# Pressure_MCU407.net
KiCad netlist of a schematic drawn in Altium Designer
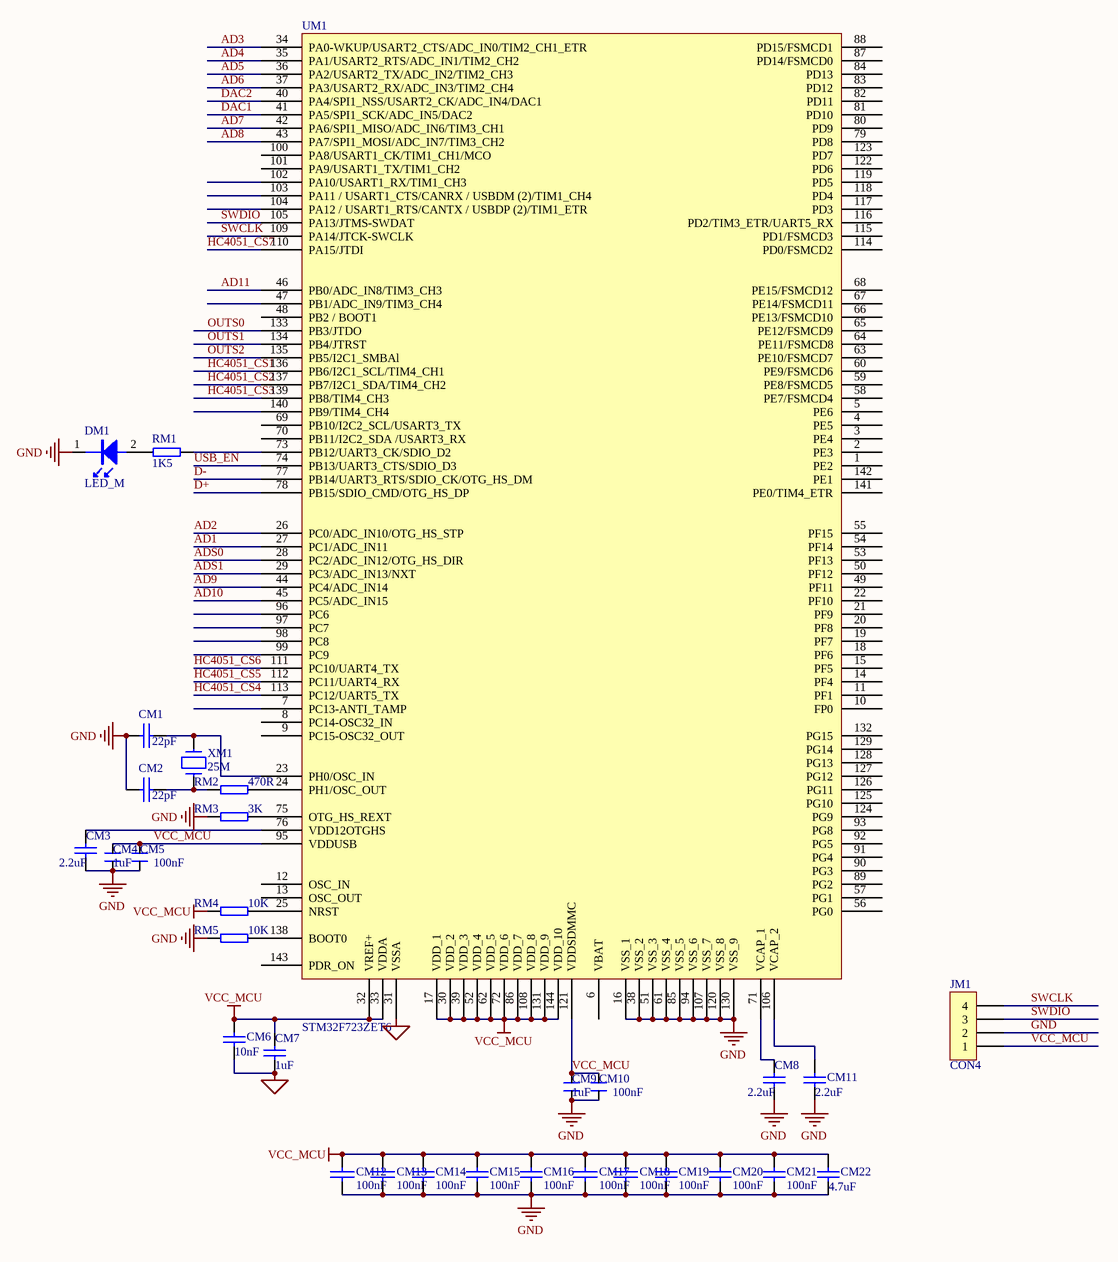
[diagram p0: Pressure_MCU407.SchDoc]

(export (version "E")
  (design (tool "Eeschema 10.0.6"))
  (components
    (comp (ref "CM1")
      (value "22pF")
      (footprint "C0603_HSC100")
      (description "Capacitor")
      (libsource (lib "*") (part "CAP"))
    )
    (comp (ref "CM2")
      (value "22pF")
      (footprint "c0603_HSC100")
      (description "Capacitor")
      (libsource (lib "*") (part "CAP"))
    )
    (comp (ref "CM3")
      (value "2.2uF")
      (footprint "C0805")
      (description "Capacitor")
      (fields (field (name "PUBLISHER") "Altium Limited"))
      (libsource (lib "*") (part "Cap"))
    )
    (comp (ref "CM4") (value "1uF") (footprint "C0603_HSC100") (libsource (lib "*") (part "CAP_M")))
    (comp (ref "CM5") (value "100nF") (footprint "C0603_HSC100") (libsource (lib "*") (part "CAP_M")))
    (comp (ref "CM6")
      (value "10nF")
      (footprint "c0603_HSC100")
      (description "Capacitor")
      (fields (field (name "PUBLISHER") "Altium Limited"))
      (libsource (lib "*") (part "Cap"))
    )
    (comp (ref "CM7")
      (value "1uF")
      (footprint "c0603_HSC100")
      (description "Capacitor")
      (fields (field (name "PUBLISHER") "Altium Limited"))
      (libsource (lib "*") (part "Cap"))
    )
    (comp (ref "CM8")
      (value "2.2uF")
      (footprint "C0805")
      (description "Capacitor")
      (fields (field (name "PUBLISHER") "Altium Limited"))
      (libsource (lib "*") (part "Cap"))
    )
    (comp (ref "CM9") (value "1uF") (footprint "C0603_HSC100") (libsource (lib "*") (part "CAP_M")))
    (comp (ref "CM10") (value "100nF") (footprint "C0603_HSC100") (libsource (lib "*") (part "CAP_M")))
    (comp (ref "CM11")
      (value "2.2uF")
      (footprint "C0805")
      (description "Capacitor")
      (fields (field (name "PUBLISHER") "Altium Limited"))
      (libsource (lib "*") (part "Cap"))
    )
    (comp (ref "CM12")
      (value "100nF")
      (footprint "c0603_HSC100")
      (description "Capacitor")
      (libsource (lib "*") (part "CAP"))
    )
    (comp (ref "CM13")
      (value "100nF")
      (footprint "c0603_HSC100")
      (description "Capacitor")
      (libsource (lib "*") (part "CAP"))
    )
    (comp (ref "CM14")
      (value "100nF")
      (footprint "c0603_HSC100")
      (description "Capacitor")
      (fields (field (name "PUBLISHER") "Altium Limited"))
      (libsource (lib "*") (part "Cap"))
    )
    (comp (ref "CM15")
      (value "100nF")
      (footprint "c0603_HSC100")
      (description "Capacitor")
      (fields (field (name "PUBLISHER") "Altium Limited"))
      (libsource (lib "*") (part "Cap"))
    )
    (comp (ref "CM16")
      (value "100nF")
      (footprint "c0603_HSC100")
      (description "Capacitor")
      (fields (field (name "PUBLISHER") "Altium Limited"))
      (libsource (lib "*") (part "Cap"))
    )
    (comp (ref "CM17")
      (value "100nF")
      (footprint "c0603_HSC100")
      (description "Capacitor")
      (libsource (lib "*") (part "CAP"))
    )
    (comp (ref "CM18")
      (value "100nF")
      (footprint "c0603_HSC100")
      (description "Capacitor")
      (libsource (lib "*") (part "CAP"))
    )
    (comp (ref "CM19")
      (value "100nF")
      (footprint "c0603_HSC100")
      (description "Capacitor")
      (fields (field (name "PUBLISHER") "Altium Limited"))
      (libsource (lib "*") (part "Cap"))
    )
    (comp (ref "CM20")
      (value "100nF")
      (footprint "c0603_HSC100")
      (description "Capacitor")
      (fields (field (name "PUBLISHER") "Altium Limited"))
      (libsource (lib "*") (part "Cap"))
    )
    (comp (ref "CM21")
      (value "100nF")
      (footprint "c0603_HSC100")
      (description "Capacitor")
      (fields (field (name "PUBLISHER") "Altium Limited"))
      (libsource (lib "*") (part "Cap"))
    )
    (comp (ref "CM22")
      (value "4.7uF")
      (footprint "C0805")
      (description "Capacitor")
      (fields (field (name "PUBLISHER") "Altium Limited"))
      (libsource (lib "*") (part "Cap"))
    )
    (comp (ref "DM1") (value "LED_M") (footprint "LED_HSC100") (libsource (lib "*") (part "LED_M")))
    (comp (ref "JM1")
      (value "CON4")
      (footprint "SIP_4M_1.27")
      (description "Connector")
      (libsource (lib "*") (part "CON4"))
    )
    (comp (ref "RM1") (value "1K5") (footprint "R0603_HSC100") (libsource (lib "*") (part "RES_M")))
    (comp (ref "RM2") (value "470R") (footprint "R0603_HSC100") (libsource (lib "*") (part "RES")))
    (comp (ref "RM3") (value "3K") (footprint "R0603_HSC100") (libsource (lib "*") (part "RES")))
    (comp (ref "RM4") (value "10K") (footprint "R0603_HSC100") (libsource (lib "*") (part "RES")))
    (comp (ref "RM5") (value "10K") (footprint "R0603_HSC100") (libsource (lib "*") (part "RES_M")))
    (comp (ref "UM1")
      (value "STM32F723ZET6")
      (footprint "LQFP144")
      (libsource (lib "MY_LIB") (part "STM32F723ZET6"))
    )
    (comp (ref "XM1")
      (value "25M")
      (footprint "CRYSTAL_SMD")
      (description "Crystal")
      (libsource (lib "*") (part "CRYSTAL"))
    )
  )
  (nets
    (net (code "1") (name "/AD1") (class "Default")
      (node (ref "UM1") (pin "27") (pinfunction "PC1/ADC_IN11_27") (pintype "passive"))
    )
    (net (code "2") (name "/AD2") (class "Default")
      (node (ref "UM1") (pin "26") (pinfunction "PC0/ADC_IN10/OTG_HS_STP_26") (pintype "passive"))
    )
    (net (code "3") (name "/AD3") (class "Default")
      (node (ref "UM1") (pin "34") (pinfunction "PA0-WKUP/USART2_CTS/ADC_IN0/TIM2_CH1_ETR_34") (pintype "passive"))
    )
    (net (code "4") (name "/AD4") (class "Default")
      (node (ref "UM1") (pin "35") (pinfunction "PA1/USART2_RTS/ADC_IN1/TIM2_CH2_35") (pintype "passive"))
    )
    (net (code "5") (name "/AD5") (class "Default")
      (node (ref "UM1") (pin "36") (pinfunction "PA2/USART2_TX/ADC_IN2/TIM2_CH3_36") (pintype "passive"))
    )
    (net (code "6") (name "/AD6") (class "Default")
      (node (ref "UM1") (pin "37") (pinfunction "PA3/USART2_RX/ADC_IN3/TIM2_CH4_37") (pintype "passive"))
    )
    (net (code "7") (name "/AD7") (class "Default")
      (node (ref "UM1") (pin "42") (pinfunction "PA6/SPI1_MISO/ADC_IN6/TIM3_CH1_42") (pintype "passive"))
    )
    (net (code "8") (name "/AD8") (class "Default")
      (node (ref "UM1") (pin "43") (pinfunction "PA7/SPI1_MOSI/ADC_IN7/TIM3_CH2_43") (pintype "passive"))
    )
    (net (code "9") (name "/AD9") (class "Default")
      (node (ref "UM1") (pin "44") (pinfunction "PC4/ADC_IN14_44") (pintype "passive"))
    )
    (net (code "10") (name "/AD10") (class "Default")
      (node (ref "UM1") (pin "45") (pinfunction "PC5/ADC_IN15_45") (pintype "passive"))
    )
    (net (code "11") (name "/AD11") (class "Default")
      (node (ref "UM1") (pin "46") (pinfunction "PB0/ADC_IN8/TIM3_CH3_46") (pintype "passive"))
    )
    (net (code "12") (name "/ADS0") (class "Default")
      (node (ref "UM1") (pin "28") (pinfunction "PC2/ADC_IN12/OTG_HS_DIR_28") (pintype "passive"))
    )
    (net (code "13") (name "/ADS1") (class "Default")
      (node (ref "UM1") (pin "29") (pinfunction "PC3/ADC_IN13/NXT_29") (pintype "passive"))
    )
    (net (code "14") (name "/D+") (class "Default")
      (node (ref "UM1") (pin "78") (pinfunction "PB15/SDIO_CMD/OTG_HS_DP_78") (pintype "passive"))
    )
    (net (code "15") (name "/D-") (class "Default")
      (node (ref "UM1") (pin "77") (pinfunction "PB14/UART3_RTS/SDIO_CK/OTG_HS_DM_77") (pintype "passive"))
    )
    (net (code "16") (name "/DAC1") (class "Default")
      (node (ref "UM1") (pin "41") (pinfunction "PA5/SPI1_SCK/ADC_IN5/DAC2_41") (pintype "passive"))
    )
    (net (code "17") (name "/DAC2") (class "Default")
      (node (ref "UM1") (pin "40") (pinfunction "PA4/SPI1_NSS/USART2_CK/ADC_IN4/DAC1_40") (pintype "passive"))
    )
    (net (code "18") (name "/HC4051_CS1") (class "Default")
      (node (ref "UM1") (pin "136") (pinfunction "PB6/I2C1_SCL/TIM4_CH1_136") (pintype "passive"))
    )
    (net (code "19") (name "/HC4051_CS2") (class "Default")
      (node (ref "UM1") (pin "137") (pinfunction "PB7/I2C1_SDA/TIM4_CH2_137") (pintype "passive"))
    )
    (net (code "20") (name "/HC4051_CS3") (class "Default")
      (node (ref "UM1") (pin "139") (pinfunction "PB8/TIM4_CH3_139") (pintype "passive"))
    )
    (net (code "21") (name "/HC4051_CS4") (class "Default")
      (node (ref "UM1") (pin "113") (pinfunction "PC12/UART5_TX_113") (pintype "passive"))
    )
    (net (code "22") (name "/HC4051_CS5") (class "Default")
      (node (ref "UM1") (pin "112") (pinfunction "PC11/UART4_RX_112") (pintype "passive"))
    )
    (net (code "23") (name "/HC4051_CS6") (class "Default")
      (node (ref "UM1") (pin "111") (pinfunction "PC10/UART4_TX_111") (pintype "passive"))
    )
    (net (code "24") (name "/HC4051_CS7") (class "Default")
      (node (ref "UM1") (pin "110") (pinfunction "PA15/JTDI_110") (pintype "passive"))
    )
    (net (code "25") (name "/OUTS0") (class "Default")
      (node (ref "UM1") (pin "133") (pinfunction "PB3/JTDO_133") (pintype "passive"))
    )
    (net (code "26") (name "/OUTS1") (class "Default")
      (node (ref "UM1") (pin "134") (pinfunction "PB4/JTRST_134") (pintype "passive"))
    )
    (net (code "27") (name "/OUTS2") (class "Default")
      (node (ref "UM1") (pin "135") (pinfunction "PB5/I2C1_SMBAl_135") (pintype "passive"))
    )
    (net (code "28") (name "/SWCLK") (class "Default")
      (node (ref "JM1") (pin "4") (pinfunction "4_4") (pintype "passive"))
      (node (ref "UM1") (pin "109") (pinfunction "PA14/JTCK-SWCLK_109") (pintype "passive"))
    )
    (net (code "29") (name "/SWDIO") (class "Default")
      (node (ref "JM1") (pin "3") (pinfunction "3_3") (pintype "passive"))
      (node (ref "UM1") (pin "105") (pinfunction "PA13/JTMS-SWDAT_105") (pintype "passive"))
    )
    (net (code "30") (name "/USB_EN") (class "Default")
      (node (ref "UM1") (pin "74") (pinfunction "PB13/UART3_CTS/SDIO_D3_74") (pintype "passive"))
    )
    (net (code "31") (name "AGND") (class "Default")
      (node (ref "CM6") (pin "2") (pinfunction "2_2") (pintype "passive"))
      (node (ref "CM7") (pin "2") (pinfunction "2_2") (pintype "passive"))
      (node (ref "UM1") (pin "31") (pinfunction "VSSA_31") (pintype "passive"))
    )
    (net (code "32") (name "GND") (class "Default")
      (node (ref "CM1") (pin "1") (pinfunction "1_1") (pintype "passive"))
      (node (ref "CM10") (pin "2") (pintype "passive"))
      (node (ref "CM11") (pin "1") (pinfunction "1_1") (pintype "passive"))
      (node (ref "CM12") (pin "2") (pinfunction "2_2") (pintype "passive"))
      (node (ref "CM13") (pin "2") (pinfunction "2_2") (pintype "passive"))
      (node (ref "CM14") (pin "1") (pinfunction "1_1") (pintype "passive"))
      (node (ref "CM15") (pin "1") (pinfunction "1_1") (pintype "passive"))
      (node (ref "CM16") (pin "1") (pinfunction "1_1") (pintype "passive"))
      (node (ref "CM17") (pin "2") (pinfunction "2_2") (pintype "passive"))
      (node (ref "CM18") (pin "2") (pinfunction "2_2") (pintype "passive"))
      (node (ref "CM19") (pin "1") (pinfunction "1_1") (pintype "passive"))
      (node (ref "CM2") (pin "1") (pinfunction "1_1") (pintype "passive"))
      (node (ref "CM20") (pin "1") (pinfunction "1_1") (pintype "passive"))
      (node (ref "CM21") (pin "1") (pinfunction "1_1") (pintype "passive"))
      (node (ref "CM22") (pin "1") (pinfunction "1_1") (pintype "passive"))
      (node (ref "CM3") (pin "1") (pinfunction "1_1") (pintype "passive"))
      (node (ref "CM4") (pin "2") (pintype "passive"))
      (node (ref "CM5") (pin "2") (pintype "passive"))
      (node (ref "CM8") (pin "1") (pinfunction "1_1") (pintype "passive"))
      (node (ref "CM9") (pin "2") (pintype "passive"))
      (node (ref "DM1") (pin "1") (pinfunction "1_1") (pintype "passive"))
      (node (ref "JM1") (pin "2") (pinfunction "2_2") (pintype "passive"))
      (node (ref "RM3") (pin "2") (pintype "passive"))
      (node (ref "RM5") (pin "1") (pintype "passive"))
      (node (ref "UM1") (pin "107") (pinfunction "VSS_7_107") (pintype "passive"))
      (node (ref "UM1") (pin "120") (pinfunction "VSS_8_120") (pintype "passive"))
      (node (ref "UM1") (pin "130") (pinfunction "VSS_9_130") (pintype "passive"))
      (node (ref "UM1") (pin "16") (pinfunction "VSS_1_16") (pintype "passive"))
      (node (ref "UM1") (pin "38") (pinfunction "VSS_2_38") (pintype "passive"))
      (node (ref "UM1") (pin "51") (pinfunction "VSS_3_51") (pintype "passive"))
      (node (ref "UM1") (pin "61") (pinfunction "VSS_4_61") (pintype "passive"))
      (node (ref "UM1") (pin "85") (pinfunction "VSS_5_85") (pintype "passive"))
      (node (ref "UM1") (pin "94") (pinfunction "VSS_6_94") (pintype "passive"))
    )
    (net (code "33") (name "Net-(CM2-Pad2)") (class "Default")
      (node (ref "CM2") (pin "2") (pinfunction "2_2") (pintype "passive"))
      (node (ref "RM2") (pin "2") (pintype "passive"))
      (node (ref "XM1") (pin "1") (pinfunction "1_1") (pintype "passive"))
    )
    (net (code "34") (name "Net-(DM1-Pad2)") (class "Default")
      (node (ref "DM1") (pin "2") (pinfunction "2_2") (pintype "passive"))
      (node (ref "RM1") (pin "2") (pintype "passive"))
    )
    (net (code "35") (name "Net-(UM1-BOOT0)") (class "Default")
      (node (ref "RM5") (pin "2") (pintype "passive"))
      (node (ref "UM1") (pin "138") (pinfunction "BOOT0_138") (pintype "passive"))
    )
    (net (code "36") (name "Net-(UM1-NRST)") (class "Default")
      (node (ref "RM4") (pin "1") (pintype "passive"))
      (node (ref "UM1") (pin "25") (pinfunction "NRST_25") (pintype "passive"))
    )
    (net (code "37") (name "Net-(UM1-OTG_HS_REXT)") (class "Default")
      (node (ref "RM3") (pin "1") (pintype "passive"))
      (node (ref "UM1") (pin "75") (pinfunction "OTG_HS_REXT_75") (pintype "passive"))
    )
    (net (code "38") (name "Net-(UM1-PB12{slash}UART3_CK{slash}SDIO_D2)") (class "Default")
      (node (ref "RM1") (pin "1") (pintype "passive"))
      (node (ref "UM1") (pin "73") (pinfunction "PB12/UART3_CK/SDIO_D2_73") (pintype "passive"))
    )
    (net (code "39") (name "Net-(UM1-PH0{slash}OSC_IN)") (class "Default")
      (node (ref "CM1") (pin "2") (pinfunction "2_2") (pintype "passive"))
      (node (ref "UM1") (pin "23") (pinfunction "PH0/OSC_IN_23") (pintype "passive"))
      (node (ref "XM1") (pin "2") (pinfunction "2_2") (pintype "passive"))
    )
    (net (code "40") (name "Net-(UM1-PH1{slash}OSC_OUT)") (class "Default")
      (node (ref "RM2") (pin "1") (pintype "passive"))
      (node (ref "UM1") (pin "24") (pinfunction "PH1/OSC_OUT_24") (pintype "passive"))
    )
    (net (code "41") (name "Net-(UM1-VCAP_1)") (class "Default")
      (node (ref "CM8") (pin "2") (pinfunction "2_2") (pintype "passive"))
      (node (ref "UM1") (pin "71") (pinfunction "VCAP_1_71") (pintype "passive"))
    )
    (net (code "42") (name "Net-(UM1-VCAP_2)") (class "Default")
      (node (ref "CM11") (pin "2") (pinfunction "2_2") (pintype "passive"))
      (node (ref "UM1") (pin "106") (pinfunction "VCAP_2_106") (pintype "passive"))
    )
    (net (code "43") (name "Net-(UM1-VDD12OTGHS)") (class "Default")
      (node (ref "CM3") (pin "2") (pinfunction "2_2") (pintype "passive"))
      (node (ref "UM1") (pin "76") (pinfunction "VDD12OTGHS_76") (pintype "passive"))
    )
    (net (code "44") (name "VCC_MCU") (class "Default")
      (node (ref "CM10") (pin "1") (pintype "passive"))
      (node (ref "CM12") (pin "1") (pinfunction "1_1") (pintype "passive"))
      (node (ref "CM13") (pin "1") (pinfunction "1_1") (pintype "passive"))
      (node (ref "CM14") (pin "2") (pinfunction "2_2") (pintype "passive"))
      (node (ref "CM15") (pin "2") (pinfunction "2_2") (pintype "passive"))
      (node (ref "CM16") (pin "2") (pinfunction "2_2") (pintype "passive"))
      (node (ref "CM17") (pin "1") (pinfunction "1_1") (pintype "passive"))
      (node (ref "CM18") (pin "1") (pinfunction "1_1") (pintype "passive"))
      (node (ref "CM19") (pin "2") (pinfunction "2_2") (pintype "passive"))
      (node (ref "CM20") (pin "2") (pinfunction "2_2") (pintype "passive"))
      (node (ref "CM21") (pin "2") (pinfunction "2_2") (pintype "passive"))
      (node (ref "CM22") (pin "2") (pinfunction "2_2") (pintype "passive"))
      (node (ref "CM4") (pin "1") (pintype "passive"))
      (node (ref "CM5") (pin "1") (pintype "passive"))
      (node (ref "CM6") (pin "1") (pinfunction "1_1") (pintype "passive"))
      (node (ref "CM7") (pin "1") (pinfunction "1_1") (pintype "passive"))
      (node (ref "CM9") (pin "1") (pintype "passive"))
      (node (ref "JM1") (pin "1") (pinfunction "1_1") (pintype "passive"))
      (node (ref "RM4") (pin "2") (pintype "passive"))
      (node (ref "UM1") (pin "108") (pinfunction "VDD_8_108") (pintype "passive"))
      (node (ref "UM1") (pin "121") (pinfunction "VDDSDMMC_121") (pintype "passive"))
      (node (ref "UM1") (pin "131") (pinfunction "VDD_9_131") (pintype "passive"))
      (node (ref "UM1") (pin "144") (pinfunction "VDD_10_144") (pintype "passive"))
      (node (ref "UM1") (pin "17") (pinfunction "VDD_1_17") (pintype "passive"))
      (node (ref "UM1") (pin "30") (pinfunction "VDD_2_30") (pintype "passive"))
      (node (ref "UM1") (pin "32") (pinfunction "VREF+_32") (pintype "passive"))
      (node (ref "UM1") (pin "33") (pinfunction "VDDA_33") (pintype "passive"))
      (node (ref "UM1") (pin "39") (pinfunction "VDD_3_39") (pintype "passive"))
      (node (ref "UM1") (pin "52") (pinfunction "VDD_4_52") (pintype "passive"))
      (node (ref "UM1") (pin "62") (pinfunction "VDD_5_62") (pintype "passive"))
      (node (ref "UM1") (pin "72") (pinfunction "VDD_6_72") (pintype "passive"))
      (node (ref "UM1") (pin "86") (pinfunction "VDD_7_86") (pintype "passive"))
      (node (ref "UM1") (pin "95") (pinfunction "VDDUSB_95") (pintype "passive"))
    )
    (net (code "45") (name "unconnected-(UM1-FP0-Pad10)") (class "Default")
      (node (ref "UM1") (pin "10") (pinfunction "FP0_10") (pintype "passive"))
    )
    (net (code "46") (name "unconnected-(UM1-OSC_IN-Pad12)") (class "Default")
      (node (ref "UM1") (pin "12") (pinfunction "OSC_IN_12") (pintype "passive"))
    )
    (net (code "47") (name "unconnected-(UM1-OSC_OUT-Pad13)") (class "Default")
      (node (ref "UM1") (pin "13") (pinfunction "OSC_OUT_13") (pintype "passive"))
    )
    (net (code "48") (name "unconnected-(UM1-PA8{slash}USART1_CK{slash}TIM1_CH1{slash}MCO-Pad100)") (class "Default")
      (node (ref "UM1") (pin "100") (pinfunction "PA8/USART1_CK/TIM1_CH1/MCO_100") (pintype "passive"))
    )
    (net (code "49") (name "unconnected-(UM1-PA9{slash}USART1_TX{slash}TIM1_CH2-Pad101)") (class "Default")
      (node (ref "UM1") (pin "101") (pinfunction "PA9/USART1_TX/TIM1_CH2_101") (pintype "passive"))
    )
    (net (code "50") (name "unconnected-(UM1-PA10{slash}USART1_RX{slash}TIM1_CH3-Pad102)") (class "Default")
      (node (ref "UM1") (pin "102") (pinfunction "PA10/USART1_RX/TIM1_CH3_102") (pintype "passive"))
    )
    (net (code "51") (name "unconnected-(UM1-PA11_{slash}_USART1_CTS{slash}CANRX_{slash}_USBDM_(2){slash}TIM1_CH4-Pad103)") (class "Default")
      (node (ref "UM1") (pin "103") (pinfunction "PA11_/_USART1_CTS/CANRX_/_USBDM_(2)/TIM1_CH4_103") (pintype "passive"))
    )
    (net (code "52") (name "unconnected-(UM1-PA12_{slash}_USART1_RTS{slash}CANTX_{slash}_USBDP_(2){slash}TIM1_ETR-Pad104)") (class "Default")
      (node (ref "UM1") (pin "104") (pinfunction "PA12_/_USART1_RTS/CANTX_/_USBDP_(2)/TIM1_ETR_104") (pintype "passive"))
    )
    (net (code "53") (name "unconnected-(UM1-PB1{slash}ADC_IN9{slash}TIM3_CH4-Pad47)") (class "Default")
      (node (ref "UM1") (pin "47") (pinfunction "PB1/ADC_IN9/TIM3_CH4_47") (pintype "passive"))
    )
    (net (code "54") (name "unconnected-(UM1-PB2_{slash}_BOOT1-Pad48)") (class "Default")
      (node (ref "UM1") (pin "48") (pinfunction "PB2_/_BOOT1_48") (pintype "passive"))
    )
    (net (code "55") (name "unconnected-(UM1-PB9{slash}TIM4_CH4-Pad140)") (class "Default")
      (node (ref "UM1") (pin "140") (pinfunction "PB9/TIM4_CH4_140") (pintype "passive"))
    )
    (net (code "56") (name "unconnected-(UM1-PB10{slash}I2C2_SCL{slash}USART3_TX-Pad69)") (class "Default")
      (node (ref "UM1") (pin "69") (pinfunction "PB10/I2C2_SCL/USART3_TX_69") (pintype "passive"))
    )
    (net (code "57") (name "unconnected-(UM1-PB11{slash}I2C2_SDA_{slash}USART3_RX-Pad70)") (class "Default")
      (node (ref "UM1") (pin "70") (pinfunction "PB11/I2C2_SDA_/USART3_RX_70") (pintype "passive"))
    )
    (net (code "58") (name "unconnected-(UM1-PC6-Pad96)") (class "Default")
      (node (ref "UM1") (pin "96") (pinfunction "PC6_96") (pintype "passive"))
    )
    (net (code "59") (name "unconnected-(UM1-PC7-Pad97)") (class "Default")
      (node (ref "UM1") (pin "97") (pinfunction "PC7_97") (pintype "passive"))
    )
    (net (code "60") (name "unconnected-(UM1-PC8-Pad98)") (class "Default")
      (node (ref "UM1") (pin "98") (pinfunction "PC8_98") (pintype "passive"))
    )
    (net (code "61") (name "unconnected-(UM1-PC9-Pad99)") (class "Default")
      (node (ref "UM1") (pin "99") (pinfunction "PC9_99") (pintype "passive"))
    )
    (net (code "62") (name "unconnected-(UM1-PC13-ANTI_TAMP-Pad7)") (class "Default")
      (node (ref "UM1") (pin "7") (pinfunction "PC13-ANTI_TAMP_7") (pintype "passive"))
    )
    (net (code "63") (name "unconnected-(UM1-PC14-OSC32_IN-Pad8)") (class "Default")
      (node (ref "UM1") (pin "8") (pinfunction "PC14-OSC32_IN_8") (pintype "passive"))
    )
    (net (code "64") (name "unconnected-(UM1-PC15-OSC32_OUT-Pad9)") (class "Default")
      (node (ref "UM1") (pin "9") (pinfunction "PC15-OSC32_OUT_9") (pintype "passive"))
    )
    (net (code "65") (name "unconnected-(UM1-PD0{slash}FSMCD2-Pad114)") (class "Default")
      (node (ref "UM1") (pin "114") (pinfunction "PD0/FSMCD2_114") (pintype "passive"))
    )
    (net (code "66") (name "unconnected-(UM1-PD1{slash}FSMCD3-Pad115)") (class "Default")
      (node (ref "UM1") (pin "115") (pinfunction "PD1/FSMCD3_115") (pintype "passive"))
    )
    (net (code "67") (name "unconnected-(UM1-PD2{slash}TIM3_ETR{slash}UART5_RX-Pad116)") (class "Default")
      (node (ref "UM1") (pin "116") (pinfunction "PD2/TIM3_ETR/UART5_RX_116") (pintype "passive"))
    )
    (net (code "68") (name "unconnected-(UM1-PD3-Pad117)") (class "Default")
      (node (ref "UM1") (pin "117") (pinfunction "PD3_117") (pintype "passive"))
    )
    (net (code "69") (name "unconnected-(UM1-PD4-Pad118)") (class "Default")
      (node (ref "UM1") (pin "118") (pinfunction "PD4_118") (pintype "passive"))
    )
    (net (code "70") (name "unconnected-(UM1-PD5-Pad119)") (class "Default")
      (node (ref "UM1") (pin "119") (pinfunction "PD5_119") (pintype "passive"))
    )
    (net (code "71") (name "unconnected-(UM1-PD6-Pad122)") (class "Default")
      (node (ref "UM1") (pin "122") (pinfunction "PD6_122") (pintype "passive"))
    )
    (net (code "72") (name "unconnected-(UM1-PD7-Pad123)") (class "Default")
      (node (ref "UM1") (pin "123") (pinfunction "PD7_123") (pintype "passive"))
    )
    (net (code "73") (name "unconnected-(UM1-PD8-Pad79)") (class "Default")
      (node (ref "UM1") (pin "79") (pinfunction "PD8_79") (pintype "passive"))
    )
    (net (code "74") (name "unconnected-(UM1-PD9-Pad80)") (class "Default")
      (node (ref "UM1") (pin "80") (pinfunction "PD9_80") (pintype "passive"))
    )
    (net (code "75") (name "unconnected-(UM1-PD10-Pad81)") (class "Default")
      (node (ref "UM1") (pin "81") (pinfunction "PD10_81") (pintype "passive"))
    )
    (net (code "76") (name "unconnected-(UM1-PD11-Pad82)") (class "Default")
      (node (ref "UM1") (pin "82") (pinfunction "PD11_82") (pintype "passive"))
    )
    (net (code "77") (name "unconnected-(UM1-PD12-Pad83)") (class "Default")
      (node (ref "UM1") (pin "83") (pinfunction "PD12_83") (pintype "passive"))
    )
    (net (code "78") (name "unconnected-(UM1-PD13-Pad84)") (class "Default")
      (node (ref "UM1") (pin "84") (pinfunction "PD13_84") (pintype "passive"))
    )
    (net (code "79") (name "unconnected-(UM1-PD14{slash}FSMCD0-Pad87)") (class "Default")
      (node (ref "UM1") (pin "87") (pinfunction "PD14/FSMCD0_87") (pintype "passive"))
    )
    (net (code "80") (name "unconnected-(UM1-PD15{slash}FSMCD1-Pad88)") (class "Default")
      (node (ref "UM1") (pin "88") (pinfunction "PD15/FSMCD1_88") (pintype "passive"))
    )
    (net (code "81") (name "unconnected-(UM1-PDR_ON-Pad143)") (class "Default")
      (node (ref "UM1") (pin "143") (pinfunction "PDR_ON_143") (pintype "passive"))
    )
    (net (code "82") (name "unconnected-(UM1-PE0{slash}TIM4_ETR-Pad141)") (class "Default")
      (node (ref "UM1") (pin "141") (pinfunction "PE0/TIM4_ETR_141") (pintype "passive"))
    )
    (net (code "83") (name "unconnected-(UM1-PE1-Pad142)") (class "Default")
      (node (ref "UM1") (pin "142") (pinfunction "PE1_142") (pintype "passive"))
    )
    (net (code "84") (name "unconnected-(UM1-PE2-Pad1)") (class "Default")
      (node (ref "UM1") (pin "1") (pinfunction "PE2_1") (pintype "passive"))
    )
    (net (code "85") (name "unconnected-(UM1-PE3-Pad2)") (class "Default")
      (node (ref "UM1") (pin "2") (pinfunction "PE3_2") (pintype "passive"))
    )
    (net (code "86") (name "unconnected-(UM1-PE4-Pad3)") (class "Default")
      (node (ref "UM1") (pin "3") (pinfunction "PE4_3") (pintype "passive"))
    )
    (net (code "87") (name "unconnected-(UM1-PE5-Pad4)") (class "Default")
      (node (ref "UM1") (pin "4") (pinfunction "PE5_4") (pintype "passive"))
    )
    (net (code "88") (name "unconnected-(UM1-PE6-Pad5)") (class "Default")
      (node (ref "UM1") (pin "5") (pinfunction "PE6_5") (pintype "passive"))
    )
    (net (code "89") (name "unconnected-(UM1-PE7{slash}FSMCD4-Pad58)") (class "Default")
      (node (ref "UM1") (pin "58") (pinfunction "PE7/FSMCD4_58") (pintype "passive"))
    )
    (net (code "90") (name "unconnected-(UM1-PE8{slash}FSMCD5-Pad59)") (class "Default")
      (node (ref "UM1") (pin "59") (pinfunction "PE8/FSMCD5_59") (pintype "passive"))
    )
    (net (code "91") (name "unconnected-(UM1-PE9{slash}FSMCD6-Pad60)") (class "Default")
      (node (ref "UM1") (pin "60") (pinfunction "PE9/FSMCD6_60") (pintype "passive"))
    )
    (net (code "92") (name "unconnected-(UM1-PE10{slash}FSMCD7-Pad63)") (class "Default")
      (node (ref "UM1") (pin "63") (pinfunction "PE10/FSMCD7_63") (pintype "passive"))
    )
    (net (code "93") (name "unconnected-(UM1-PE11{slash}FSMCD8-Pad64)") (class "Default")
      (node (ref "UM1") (pin "64") (pinfunction "PE11/FSMCD8_64") (pintype "passive"))
    )
    (net (code "94") (name "unconnected-(UM1-PE12{slash}FSMCD9-Pad65)") (class "Default")
      (node (ref "UM1") (pin "65") (pinfunction "PE12/FSMCD9_65") (pintype "passive"))
    )
    (net (code "95") (name "unconnected-(UM1-PE13{slash}FSMCD10-Pad66)") (class "Default")
      (node (ref "UM1") (pin "66") (pinfunction "PE13/FSMCD10_66") (pintype "passive"))
    )
    (net (code "96") (name "unconnected-(UM1-PE14{slash}FSMCD11-Pad67)") (class "Default")
      (node (ref "UM1") (pin "67") (pinfunction "PE14/FSMCD11_67") (pintype "passive"))
    )
    (net (code "97") (name "unconnected-(UM1-PE15{slash}FSMCD12-Pad68)") (class "Default")
      (node (ref "UM1") (pin "68") (pinfunction "PE15/FSMCD12_68") (pintype "passive"))
    )
    (net (code "98") (name "unconnected-(UM1-PF1-Pad11)") (class "Default")
      (node (ref "UM1") (pin "11") (pinfunction "PF1_11") (pintype "passive"))
    )
    (net (code "99") (name "unconnected-(UM1-PF4-Pad14)") (class "Default")
      (node (ref "UM1") (pin "14") (pinfunction "PF4_14") (pintype "passive"))
    )
    (net (code "100") (name "unconnected-(UM1-PF5-Pad15)") (class "Default")
      (node (ref "UM1") (pin "15") (pinfunction "PF5_15") (pintype "passive"))
    )
    (net (code "101") (name "unconnected-(UM1-PF6-Pad18)") (class "Default")
      (node (ref "UM1") (pin "18") (pinfunction "PF6_18") (pintype "passive"))
    )
    (net (code "102") (name "unconnected-(UM1-PF7-Pad19)") (class "Default")
      (node (ref "UM1") (pin "19") (pinfunction "PF7_19") (pintype "passive"))
    )
    (net (code "103") (name "unconnected-(UM1-PF8-Pad20)") (class "Default")
      (node (ref "UM1") (pin "20") (pinfunction "PF8_20") (pintype "passive"))
    )
    (net (code "104") (name "unconnected-(UM1-PF9-Pad21)") (class "Default")
      (node (ref "UM1") (pin "21") (pinfunction "PF9_21") (pintype "passive"))
    )
    (net (code "105") (name "unconnected-(UM1-PF10-Pad22)") (class "Default")
      (node (ref "UM1") (pin "22") (pinfunction "PF10_22") (pintype "passive"))
    )
    (net (code "106") (name "unconnected-(UM1-PF11-Pad49)") (class "Default")
      (node (ref "UM1") (pin "49") (pinfunction "PF11_49") (pintype "passive"))
    )
    (net (code "107") (name "unconnected-(UM1-PF12-Pad50)") (class "Default")
      (node (ref "UM1") (pin "50") (pinfunction "PF12_50") (pintype "passive"))
    )
    (net (code "108") (name "unconnected-(UM1-PF13-Pad53)") (class "Default")
      (node (ref "UM1") (pin "53") (pinfunction "PF13_53") (pintype "passive"))
    )
    (net (code "109") (name "unconnected-(UM1-PF14-Pad54)") (class "Default")
      (node (ref "UM1") (pin "54") (pinfunction "PF14_54") (pintype "passive"))
    )
    (net (code "110") (name "unconnected-(UM1-PF15-Pad55)") (class "Default")
      (node (ref "UM1") (pin "55") (pinfunction "PF15_55") (pintype "passive"))
    )
    (net (code "111") (name "unconnected-(UM1-PG0-Pad56)") (class "Default")
      (node (ref "UM1") (pin "56") (pinfunction "PG0_56") (pintype "passive"))
    )
    (net (code "112") (name "unconnected-(UM1-PG1-Pad57)") (class "Default")
      (node (ref "UM1") (pin "57") (pinfunction "PG1_57") (pintype "passive"))
    )
    (net (code "113") (name "unconnected-(UM1-PG2-Pad89)") (class "Default")
      (node (ref "UM1") (pin "89") (pinfunction "PG2_89") (pintype "passive"))
    )
    (net (code "114") (name "unconnected-(UM1-PG3-Pad90)") (class "Default")
      (node (ref "UM1") (pin "90") (pinfunction "PG3_90") (pintype "passive"))
    )
    (net (code "115") (name "unconnected-(UM1-PG4-Pad91)") (class "Default")
      (node (ref "UM1") (pin "91") (pinfunction "PG4_91") (pintype "passive"))
    )
    (net (code "116") (name "unconnected-(UM1-PG5-Pad92)") (class "Default")
      (node (ref "UM1") (pin "92") (pinfunction "PG5_92") (pintype "passive"))
    )
    (net (code "117") (name "unconnected-(UM1-PG8-Pad93)") (class "Default")
      (node (ref "UM1") (pin "93") (pinfunction "PG8_93") (pintype "passive"))
    )
    (net (code "118") (name "unconnected-(UM1-PG9-Pad124)") (class "Default")
      (node (ref "UM1") (pin "124") (pinfunction "PG9_124") (pintype "passive"))
    )
    (net (code "119") (name "unconnected-(UM1-PG10-Pad125)") (class "Default")
      (node (ref "UM1") (pin "125") (pinfunction "PG10_125") (pintype "passive"))
    )
    (net (code "120") (name "unconnected-(UM1-PG11-Pad126)") (class "Default")
      (node (ref "UM1") (pin "126") (pinfunction "PG11_126") (pintype "passive"))
    )
    (net (code "121") (name "unconnected-(UM1-PG12-Pad127)") (class "Default")
      (node (ref "UM1") (pin "127") (pinfunction "PG12_127") (pintype "passive"))
    )
    (net (code "122") (name "unconnected-(UM1-PG13-Pad128)") (class "Default")
      (node (ref "UM1") (pin "128") (pinfunction "PG13_128") (pintype "passive"))
    )
    (net (code "123") (name "unconnected-(UM1-PG14-Pad129)") (class "Default")
      (node (ref "UM1") (pin "129") (pinfunction "PG14_129") (pintype "passive"))
    )
    (net (code "124") (name "unconnected-(UM1-PG15-Pad132)") (class "Default")
      (node (ref "UM1") (pin "132") (pinfunction "PG15_132") (pintype "passive"))
    )
    (net (code "125") (name "unconnected-(UM1-VBAT-Pad6)") (class "Default")
      (node (ref "UM1") (pin "6") (pinfunction "VBAT_6") (pintype "passive"))
    )
  )
)
